# CW6680E_LQFP48_BT_Boombox_S10_V1_0.net
KiCad netlist of a schematic drawn in Altium Designer
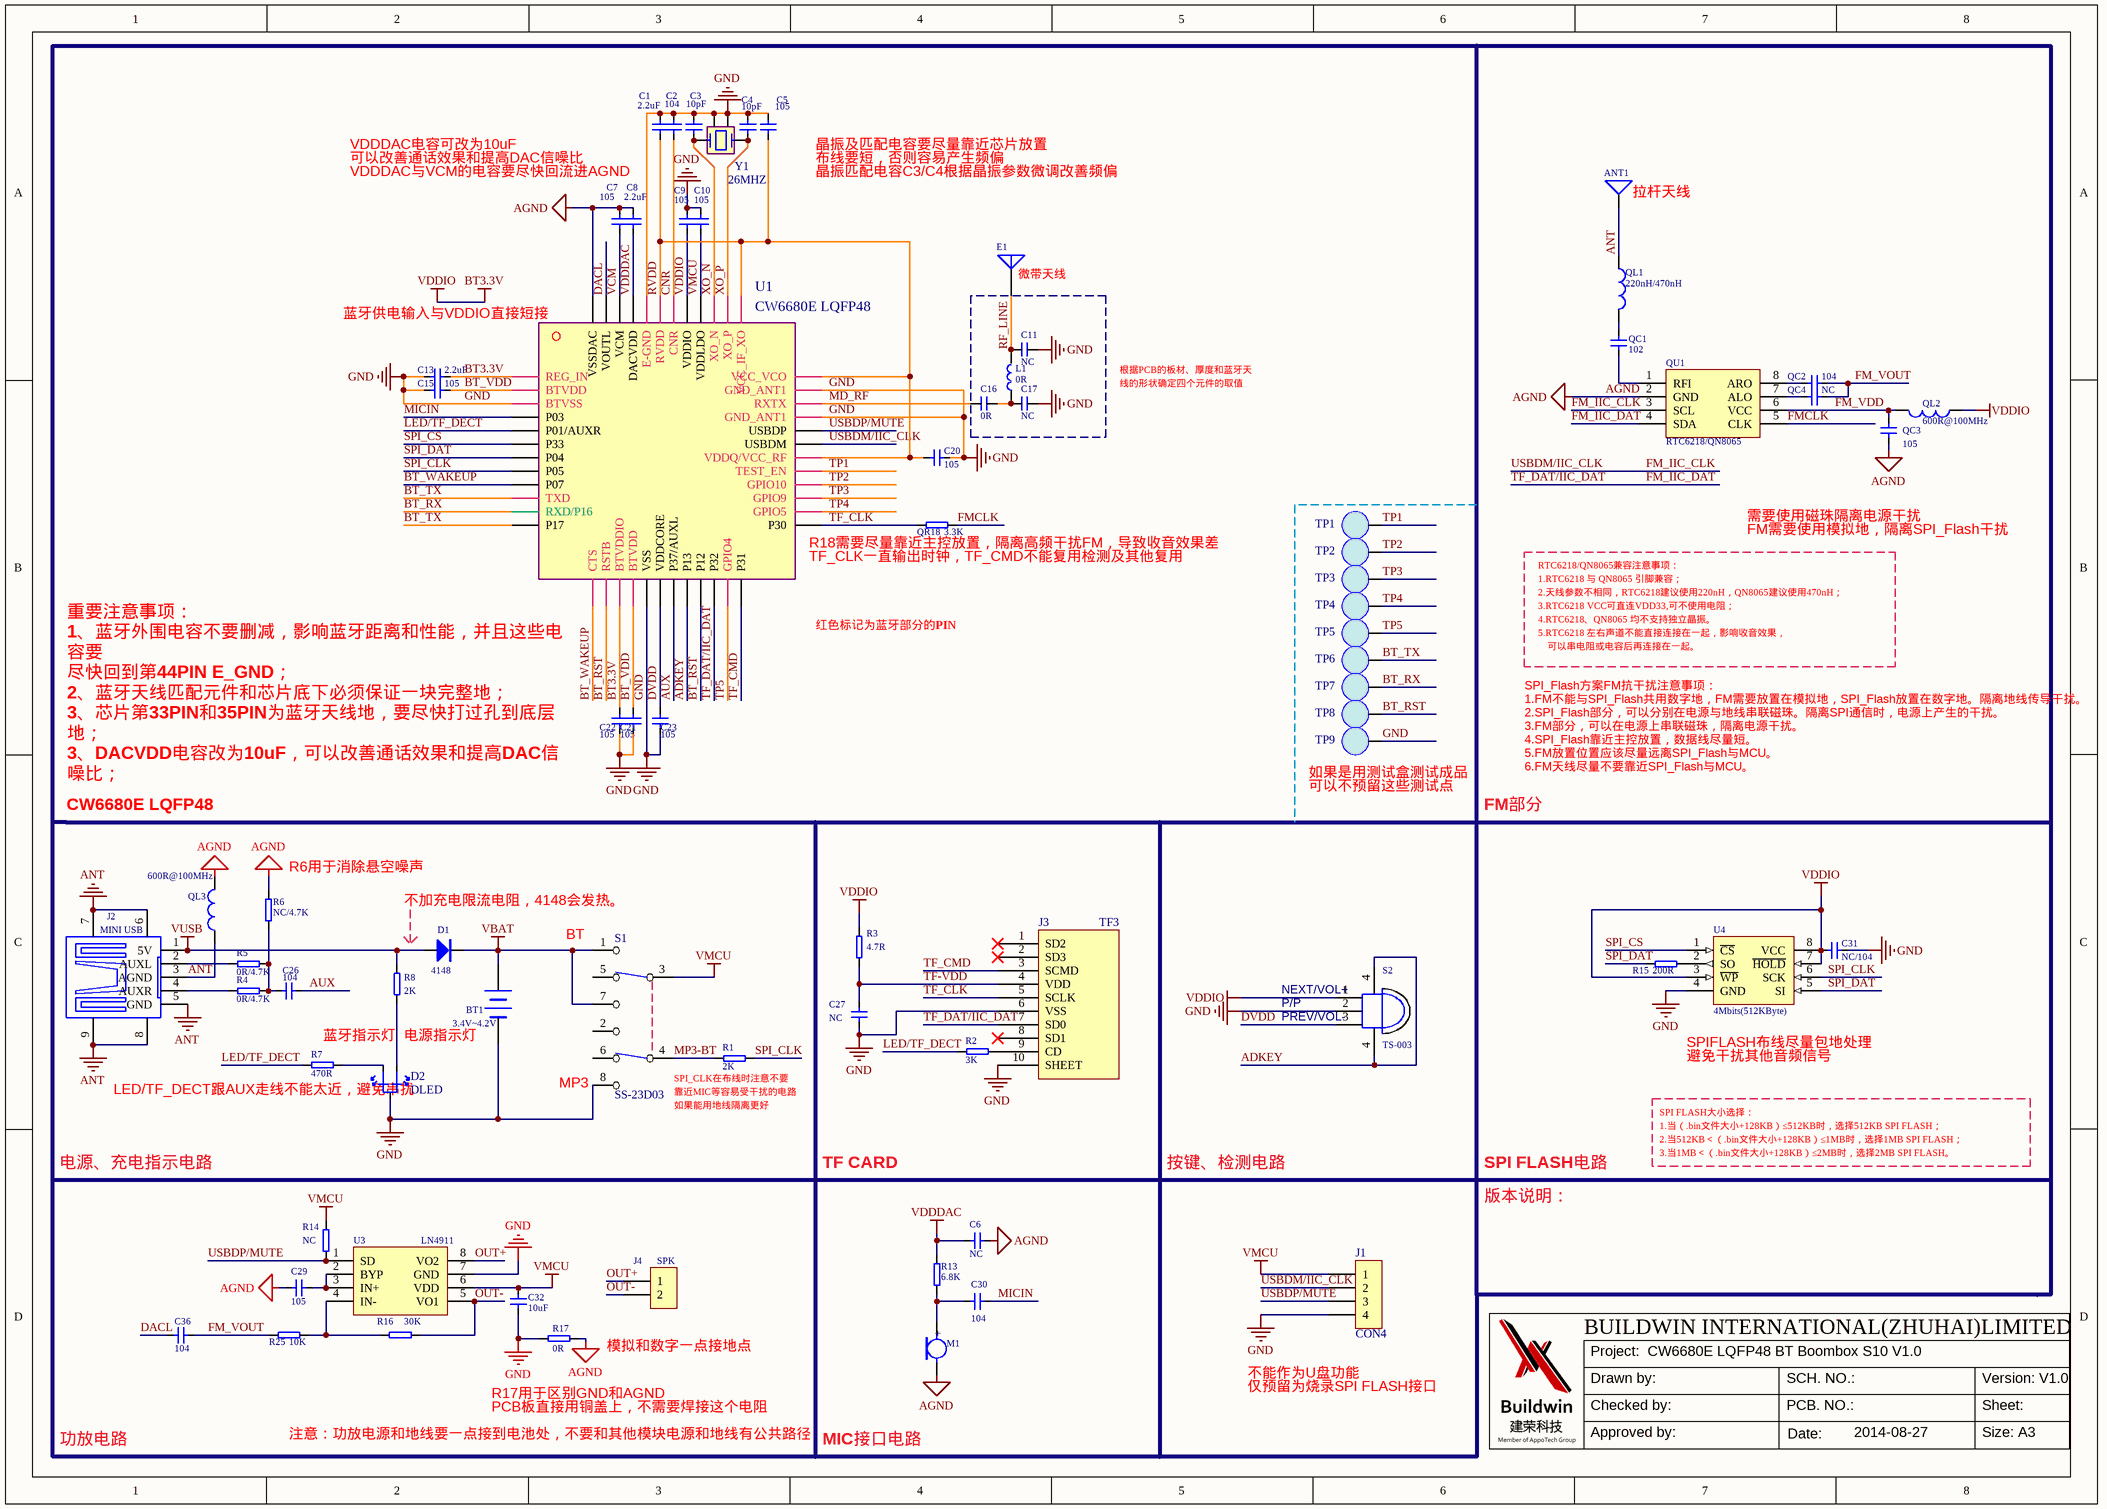
[diagram p0: CW6680E LQFP48 BT Boombox S10 V1.0.SchDoc]

(export (version "E")
  (design (tool "Eeschema 10.0.6"))
  (components
    (comp (ref "ANT1") (value "~") (footprint "ANT") (libsource (lib "*") (part "ANT")))
    (comp (ref "BT1")
      (value "3.4V~4.2V")
      (footprint "SIP2")
      (description "Battery")
      (libsource (lib "*") (part "BATTERY"))
    )
    (comp (ref "C1")
      (value "2.2uF")
      (footprint "C0603")
      (description "Capacitor")
      (libsource (lib "Common SCH") (part "CAP"))
    )
    (comp (ref "C2")
      (value "104")
      (footprint "C0603")
      (description "Capacitor")
      (libsource (lib "Common SCH") (part "CAP"))
    )
    (comp (ref "C3")
      (value "10pF")
      (footprint "C0603")
      (description "Capacitor")
      (libsource (lib "Common SCH") (part "CAP"))
    )
    (comp (ref "C4")
      (value "10pF")
      (footprint "C0603")
      (description "Capacitor")
      (libsource (lib "Common SCH") (part "CAP"))
    )
    (comp (ref "C5")
      (value "105")
      (footprint "C0603")
      (description "Capacitor")
      (libsource (lib "Common SCH") (part "CAP"))
    )
    (comp (ref "C6")
      (value "NC")
      (footprint "C0603")
      (description "Capacitor")
      (libsource (lib "*") (part "CAP"))
    )
    (comp (ref "C7")
      (value "105")
      (footprint "C0603")
      (description "Capacitor")
      (libsource (lib "Common SCH") (part "CAP"))
    )
    (comp (ref "C8")
      (value "2.2uF")
      (footprint "C0603")
      (description "Capacitor")
      (libsource (lib "Common SCH") (part "CAP"))
    )
    (comp (ref "C9")
      (value "105")
      (footprint "C0603")
      (description "Capacitor")
      (libsource (lib "Common SCH") (part "CAP"))
    )
    (comp (ref "C10")
      (value "105")
      (footprint "C0603")
      (description "Capacitor")
      (libsource (lib "Common SCH") (part "CAP"))
    )
    (comp (ref "C11")
      (value "NC")
      (footprint "C0603")
      (description "0402 CER CAP NCpF 50V +/-10%")
      (libsource (lib "*") (part "CAP_C"))
    )
    (comp (ref "C13")
      (value "2.2uF")
      (footprint "C0603")
      (description "Capacitor")
      (libsource (lib "Common SCH") (part "CAP"))
    )
    (comp (ref "C15")
      (value "105")
      (footprint "C0603")
      (description "Capacitor")
      (libsource (lib "Common SCH") (part "CAP"))
    )
    (comp (ref "C16")
      (value "0R")
      (footprint "C0603")
      (description "0402 CER CAP ?pF 50V +/-10%")
      (libsource (lib "*") (part "CAP_C"))
    )
    (comp (ref "C17")
      (value "NC")
      (footprint "C0603")
      (description "0402 CER CAP NCpF 50V +/-10%")
      (libsource (lib "*") (part "CAP_C"))
    )
    (comp (ref "C20")
      (value "105")
      (footprint "C0603")
      (description "Capacitor")
      (libsource (lib "Common SCH") (part "CAP"))
    )
    (comp (ref "C21")
      (value "105")
      (footprint "C0603")
      (description "Capacitor")
      (libsource (lib "*") (part "CAP"))
    )
    (comp (ref "C22")
      (value "105")
      (footprint "C0603")
      (description "Capacitor")
      (libsource (lib "*") (part "CAP"))
    )
    (comp (ref "C23")
      (value "105")
      (footprint "C0603")
      (description "Capacitor")
      (libsource (lib "Common SCH") (part "CAP"))
    )
    (comp (ref "C26")
      (value "104")
      (footprint "C0603")
      (description "Capacitor")
      (libsource (lib "*") (part "CAP"))
    )
    (comp (ref "C27")
      (value "NC")
      (footprint "C0603")
      (description "Capacitor")
      (libsource (lib "*") (part "CAP"))
    )
    (comp (ref "C29")
      (value "105")
      (footprint "C0603")
      (description "Capacitor")
      (libsource (lib "*") (part "CAP"))
    )
    (comp (ref "C30")
      (value "104")
      (footprint "C0603")
      (description "Capacitor")
      (libsource (lib "*") (part "CAP"))
    )
    (comp (ref "C31")
      (value "NC/104")
      (footprint "C0603")
      (description "Capacitor")
      (libsource (lib "Common SCH") (part "CAP"))
    )
    (comp (ref "C32")
      (value "10uF")
      (footprint "C0805")
      (description "Capacitor")
      (libsource (lib "*") (part "CAP"))
    )
    (comp (ref "C36")
      (value "104")
      (footprint "C0603")
      (description "Capacitor")
      (libsource (lib "*") (part "CAP"))
    )
    (comp (ref "D1")
      (value "4148")
      (footprint "DO-214")
      (description "Diode")
      (libsource (lib "*") (part "DIODE"))
    )
    (comp (ref "D2")
      (value "DLED")
      (footprint "LED-R&B")
      (description "双色灯 插件 共阴")
      (libsource (lib "LHLC-BDG-8051-V1.0") (part "DLED"))
    )
    (comp (ref "E1")
      (value "~")
      (footprint "ant_pifa")
      (description "Generic Antenna")
      (fields (field (name "PUBLISHER") "Altium Limited"))
      (libsource (lib "*") (part "Antenna"))
    )
    (comp (ref "J1")
      (value "CON4")
      (footprint "SIP4")
      (description "Connector")
      (libsource (lib "BW CONNECTOR SCH") (part "CON4"))
    )
    (comp (ref "J2")
      (value "MINI USB")
      (footprint "MINI-USB-B")
      (libsource (lib "BW SCH") (part "Mini USB-F"))
    )
    (comp (ref "J3") (value "TF3") (footprint "TFCARD") (libsource (lib "*") (part "TF")))
    (comp (ref "J4")
      (value "SPK")
      (footprint "SIP2")
      (description "Connector")
      (libsource (lib "*") (part "CON2"))
    )
    (comp (ref "L1")
      (value "0R")
      (footprint "L0603")
      (description "0 OHM")
      (libsource (lib "*") (part "INDUCTOR"))
    )
    (comp (ref "M1")
      (value "MIC")
      (footprint "MIC-4022")
      (description "Microphone")
      (libsource (lib "*") (part "MICROPHONE2"))
    )
    (comp (ref "QC1")
      (value "102")
      (footprint "C0603")
      (description "Capacitor")
      (libsource (lib "") (part "CAP_1"))
    )
    (comp (ref "QC2")
      (value "104")
      (footprint "C0603")
      (description "Capacitor")
      (libsource (lib "") (part "CAP_2"))
    )
    (comp (ref "QC3")
      (value "105")
      (footprint "C0603")
      (description "Capacitor")
      (libsource (lib "") (part "CAP_2"))
    )
    (comp (ref "QC4")
      (value "NC")
      (footprint "C0603")
      (description "Capacitor")
      (libsource (lib "") (part "CAP_2"))
    )
    (comp (ref "QL1") (value "220nH/470nH") (footprint "L0603") (libsource (lib "") (part "INDUCTOR_1")))
    (comp (ref "QL2") (value "600R@100MHz") (footprint "L0603") (libsource (lib "") (part "INDUCTOR_3")))
    (comp (ref "QL3") (value "600R@100MHz") (footprint "L0603") (libsource (lib "") (part "INDUCTOR_2")))
    (comp (ref "QR18") (value "3.3K") (footprint "R0603") (libsource (lib "*") (part "RES2")))
    (comp (ref "QU1")
      (value "RTC6218/QN8065")
      (footprint "SO-8")
      (libsource (lib "AX2053B Cola Demo V1.2") (part "QN8075"))
    )
    (comp (ref "R1") (value "2K") (footprint "R0603") (libsource (lib "*") (part "RES2")))
    (comp (ref "R2") (value "3K") (footprint "R0603") (libsource (lib "*") (part "RES2")))
    (comp (ref "R3") (value "4.7R") (footprint "R0603") (libsource (lib "*") (part "RES2")))
    (comp (ref "R4") (value "0R/4.7K") (footprint "R0603") (libsource (lib "*") (part "RES2")))
    (comp (ref "R5") (value "0R/4.7K") (footprint "R0603") (libsource (lib "*") (part "RES2")))
    (comp (ref "R6") (value "NC/4.7K") (footprint "R0603") (libsource (lib "*") (part "RES2")))
    (comp (ref "R7") (value "470R") (footprint "R0603") (libsource (lib "*") (part "RES2")))
    (comp (ref "R8") (value "2K") (footprint "R0603") (libsource (lib "*") (part "RES2")))
    (comp (ref "R13") (value "6.8K") (footprint "R0603") (libsource (lib "*") (part "RES2")))
    (comp (ref "R14") (value "NC") (footprint "R0603") (libsource (lib "*") (part "RES2")))
    (comp (ref "R15") (value "200R") (footprint "R0603") (libsource (lib "Common SCH") (part "RES2")))
    (comp (ref "R16") (value "30K") (footprint "R0603") (libsource (lib "*") (part "RES2")))
    (comp (ref "R17") (value "0R") (footprint "R0603") (libsource (lib "") (part "RES2_1")))
    (comp (ref "R25") (value "10K") (footprint "R0603") (libsource (lib "*") (part "RES2")))
    (comp (ref "S1")
      (value "SS-23D03")
      (footprint "3ND")
      (libsource (lib "S10-（AX2227+CW6639）V1.0") (part "SW-DPST"))
    )
    (comp (ref "S2") (value "TS-003") (footprint "KEY_BL") (libsource (lib "Schlib1") (part "TS-003")))
    (comp (ref "TP1")
      (value "TestPoint")
      (footprint "TP01")
      (libsource (lib "buildwin_BT") (part "TestPoint"))
    )
    (comp (ref "TP2")
      (value "TestPoint")
      (footprint "TP01")
      (libsource (lib "buildwin_BT") (part "TestPoint"))
    )
    (comp (ref "TP3")
      (value "TestPoint")
      (footprint "TP01")
      (libsource (lib "buildwin_BT") (part "TestPoint"))
    )
    (comp (ref "TP4")
      (value "TestPoint")
      (footprint "TP01")
      (libsource (lib "buildwin_BT") (part "TestPoint"))
    )
    (comp (ref "TP5")
      (value "TestPoint")
      (footprint "TP01")
      (libsource (lib "buildwin_BT") (part "TestPoint"))
    )
    (comp (ref "TP6")
      (value "TestPoint")
      (footprint "TP01")
      (libsource (lib "buildwin_BT") (part "TestPoint"))
    )
    (comp (ref "TP7")
      (value "TestPoint")
      (footprint "TP01")
      (libsource (lib "buildwin_BT") (part "TestPoint"))
    )
    (comp (ref "TP8")
      (value "TestPoint")
      (footprint "TP01")
      (libsource (lib "buildwin_BT") (part "TestPoint"))
    )
    (comp (ref "TP9")
      (value "TestPoint")
      (footprint "TP01")
      (libsource (lib "buildwin_BT") (part "TestPoint"))
    )
    (comp (ref "U1") (value "CW6680E LQFP48") (footprint "LQFP48-7*7") (libsource (lib "*") (part "BT8202")))
    (comp (ref "U3") (value "LN4911") (footprint "SO-8") (libsource (lib "*") (part "4871")))
    (comp (ref "U4")
      (value "4Mbits(512KByte)")
      (footprint "SO-8/8W")
      (libsource (lib "*") (part "SPI FLASH"))
    )
    (comp (ref "Y1") (value "26MHZ") (footprint "26m") (libsource (lib "*") (part "26MHZ")))
  )
  (nets
    (net (code "2") (name "/ADKEY") (class "Default")
      (node (ref "S2") (pin "4") (pinfunction "4_4") (pintype "passive"))
      (node (ref "U1") (pin "20") (pinfunction "P13_20") (pintype "passive"))
    )
    (net (code "3") (name "/AUX") (class "Default")
      (node (ref "C26") (pin "1") (pinfunction "1_1") (pintype "passive"))
      (node (ref "U1") (pin "19") (pinfunction "P37/AUXL_19") (pintype "passive"))
    )
    (net (code "4") (name "/BT_RST") (class "Default")
      (node (ref "TP8") (pin "1") (pinfunction "1_1") (pintype "power_in"))
      (node (ref "U1") (pin "14") (pinfunction "RSTB_14") (pintype "passive"))
      (node (ref "U1") (pin "21") (pinfunction "P12_21") (pintype "passive"))
    )
    (net (code "5") (name "/BT_RX") (class "Default")
      (node (ref "TP7") (pin "1") (pinfunction "1_1") (pintype "power_in"))
      (node (ref "U1") (pin "11") (pinfunction "RXD/P16_11") (pintype "passive"))
    )
    (net (code "6") (name "/BT_TX") (class "Default")
      (node (ref "TP6") (pin "1") (pinfunction "1_1") (pintype "power_in"))
      (node (ref "U1") (pin "10") (pinfunction "TXD_10") (pintype "passive"))
      (node (ref "U1") (pin "12") (pinfunction "P17_12") (pintype "passive"))
    )
    (net (code "7") (name "/BT_VDD") (class "Default")
      (node (ref "C15") (pin "2") (pinfunction "2_2") (pintype "passive"))
      (node (ref "C21") (pin "1") (pinfunction "1_1") (pintype "passive"))
      (node (ref "U1") (pin "16") (pinfunction "BTVDD_16") (pintype "passive"))
      (node (ref "U1") (pin "2") (pinfunction "BTVDD_2") (pintype "passive"))
    )
    (net (code "8") (name "/BT_WAKEUP") (class "Default")
      (node (ref "U1") (pin "13") (pinfunction "CTS_13") (pintype "passive"))
      (node (ref "U1") (pin "9") (pinfunction "P07_9") (pintype "passive"))
    )
    (net (code "9") (name "/CNR") (class "Default")
      (node (ref "C2") (pin "1") (pinfunction "1_1") (pintype "passive"))
      (node (ref "U1") (pin "42") (pinfunction "CNR_42") (pintype "passive"))
    )
    (net (code "10") (name "/DACL") (class "Default")
      (node (ref "C36") (pin "1") (pinfunction "1_1") (pintype "passive"))
      (node (ref "U1") (pin "47") (pinfunction "VOUTL_47") (pintype "passive"))
    )
    (net (code "11") (name "/DVDD") (class "Default")
      (node (ref "C23") (pin "1") (pinfunction "1_1") (pintype "passive"))
      (node (ref "S2") (pin "3") (pinfunction "3_3") (pintype "passive"))
      (node (ref "U1") (pin "18") (pinfunction "VDDCORE_18") (pintype "passive"))
    )
    (net (code "12") (name "/FMCLK") (class "Default")
      (node (ref "QR18") (pin "1") (pinfunction "1_1") (pintype "passive"))
      (node (ref "QU1") (pin "5") (pinfunction "CLK_5") (pintype "passive"))
    )
    (net (code "13") (name "/FM_IIC_CLK") (class "Default")
      (node (ref "J1") (pin "2") (pinfunction "2_2") (pintype "passive"))
      (node (ref "QU1") (pin "3") (pinfunction "SCL_3") (pintype "passive"))
      (node (ref "U1") (pin "31") (pinfunction "USBDM_31") (pintype "passive"))
    )
    (net (code "14") (name "/FM_IIC_DAT") (class "Default")
      (node (ref "J3") (pin "7") (pinfunction "SD0_7") (pintype "passive"))
      (node (ref "QU1") (pin "4") (pinfunction "SDA_4") (pintype "passive"))
      (node (ref "U1") (pin "22") (pinfunction "P32_22") (pintype "passive"))
    )
    (net (code "15") (name "/FM_VDD") (class "Default")
      (node (ref "QC3") (pin "1") (pinfunction "1_1") (pintype "passive"))
      (node (ref "QL2") (pin "1") (pinfunction "1_1") (pintype "passive"))
      (node (ref "QU1") (pin "6") (pinfunction "VCC_6") (pintype "passive"))
    )
    (net (code "16") (name "/FM_VOUT") (class "Default")
      (node (ref "C36") (pin "2") (pinfunction "2_2") (pintype "passive"))
      (node (ref "QC2") (pin "1") (pinfunction "1_1") (pintype "passive"))
      (node (ref "QC4") (pin "1") (pinfunction "1_1") (pintype "passive"))
      (node (ref "R25") (pin "2") (pinfunction "2_2") (pintype "passive"))
    )
    (net (code "17") (name "/LED{slash}TF_DECT") (class "Default")
      (node (ref "R2") (pin "1") (pinfunction "1_1") (pintype "passive"))
      (node (ref "R7") (pin "2") (pinfunction "2_2") (pintype "passive"))
      (node (ref "U1") (pin "5") (pinfunction "P01/AUXR_5") (pintype "passive"))
    )
    (net (code "18") (name "/MD_RF") (class "Default")
      (node (ref "C16") (pin "2") (pintype "passive"))
      (node (ref "U1") (pin "34") (pinfunction "RXTX_34") (pintype "passive"))
    )
    (net (code "19") (name "/MICIN") (class "Default")
      (node (ref "C30") (pin "1") (pinfunction "1_1") (pintype "passive"))
      (node (ref "U1") (pin "4") (pinfunction "P03_4") (pintype "passive"))
    )
    (net (code "20") (name "/MP3-BT") (class "Default")
      (node (ref "R1") (pin "2") (pinfunction "2_2") (pintype "passive"))
      (node (ref "S1") (pin "4") (pinfunction "4_4") (pintype "passive"))
    )
    (net (code "21") (name "/OUT+") (class "Default")
      (node (ref "J4") (pin "1") (pinfunction "1_1") (pintype "passive"))
      (node (ref "U3") (pin "8") (pinfunction "VO2_8") (pintype "passive"))
    )
    (net (code "22") (name "/OUT-") (class "Default")
      (node (ref "J4") (pin "2") (pinfunction "2_2") (pintype "passive"))
      (node (ref "R16") (pin "1") (pinfunction "1_1") (pintype "passive"))
      (node (ref "U3") (pin "5") (pinfunction "VO1_5") (pintype "passive"))
    )
    (net (code "23") (name "/RF_LINE") (class "Default")
      (node (ref "C11") (pin "1") (pintype "passive"))
      (node (ref "E1") (pin "1") (pinfunction "A_1") (pintype "passive"))
      (node (ref "L1") (pin "2") (pinfunction "2_2") (pintype "passive"))
    )
    (net (code "24") (name "/RVDD") (class "Default")
      (node (ref "C1") (pin "1") (pinfunction "1_1") (pintype "passive"))
      (node (ref "C20") (pin "1") (pinfunction "1_1") (pintype "passive"))
      (node (ref "C5") (pin "2") (pinfunction "2_2") (pintype "passive"))
      (node (ref "U1") (pin "30") (pinfunction "VDDQ/VCC_RF_30") (pintype "passive"))
      (node (ref "U1") (pin "36") (pinfunction "VCC_VCO_36") (pintype "passive"))
      (node (ref "U1") (pin "37") (pinfunction "VCC_IF_XO_37") (pintype "passive"))
      (node (ref "U1") (pin "43") (pinfunction "RVDD_43") (pintype "passive"))
    )
    (net (code "25") (name "/SPI_CLK") (class "Default")
      (node (ref "R1") (pin "1") (pinfunction "1_1") (pintype "passive"))
      (node (ref "U1") (pin "8") (pinfunction "P05_8") (pintype "passive"))
      (node (ref "U4") (pin "6") (pinfunction "SCK_6") (pintype "input"))
    )
    (net (code "26") (name "/SPI_CS") (class "Default")
      (node (ref "U1") (pin "6") (pinfunction "P33_6") (pintype "passive"))
      (node (ref "U4") (pin "1") (pinfunction "~{CS}_1") (pintype "input"))
    )
    (net (code "27") (name "/SPI_DAT") (class "Default")
      (node (ref "R15") (pin "2") (pinfunction "2_2") (pintype "passive"))
      (node (ref "U1") (pin "7") (pinfunction "P04_7") (pintype "passive"))
      (node (ref "U4") (pin "5") (pinfunction "SI_5") (pintype "input"))
    )
    (net (code "28") (name "/TF-VDD") (class "Default")
      (node (ref "C27") (pin "1") (pinfunction "1_1") (pintype "passive"))
      (node (ref "J3") (pin "4") (pinfunction "VDD_4") (pintype "passive"))
      (node (ref "R3") (pin "1") (pinfunction "1_1") (pintype "passive"))
    )
    (net (code "29") (name "/TF_CLK") (class "Default")
      (node (ref "J3") (pin "5") (pinfunction "SCLK_5") (pintype "passive"))
      (node (ref "QR18") (pin "2") (pinfunction "2_2") (pintype "passive"))
      (node (ref "U1") (pin "25") (pinfunction "P30_25") (pintype "passive"))
    )
    (net (code "30") (name "/TF_CMD") (class "Default")
      (node (ref "J3") (pin "3") (pinfunction "SCMD_3") (pintype "passive"))
      (node (ref "U1") (pin "24") (pinfunction "P31_24") (pintype "passive"))
    )
    (net (code "31") (name "/TP1") (class "Default")
      (node (ref "TP1") (pin "1") (pinfunction "1_1") (pintype "power_in"))
      (node (ref "U1") (pin "29") (pinfunction "TEST_EN_29") (pintype "passive"))
    )
    (net (code "32") (name "/TP2") (class "Default")
      (node (ref "TP2") (pin "1") (pinfunction "1_1") (pintype "power_in"))
      (node (ref "U1") (pin "28") (pinfunction "GPIO10_28") (pintype "passive"))
    )
    (net (code "33") (name "/TP3") (class "Default")
      (node (ref "TP3") (pin "1") (pinfunction "1_1") (pintype "power_in"))
      (node (ref "U1") (pin "27") (pinfunction "GPIO9_27") (pintype "passive"))
    )
    (net (code "34") (name "/TP4") (class "Default")
      (node (ref "TP4") (pin "1") (pinfunction "1_1") (pintype "power_in"))
      (node (ref "U1") (pin "26") (pinfunction "GPIO5_26") (pintype "passive"))
    )
    (net (code "35") (name "/TP5") (class "Default")
      (node (ref "TP5") (pin "1") (pinfunction "1_1") (pintype "power_in"))
      (node (ref "U1") (pin "23") (pinfunction "GPIO4_23") (pintype "passive"))
    )
    (net (code "36") (name "/USBDP{slash}MUTE") (class "Default")
      (node (ref "J1") (pin "3") (pinfunction "3_3") (pintype "passive"))
      (node (ref "R14") (pin "1") (pinfunction "1_1") (pintype "passive"))
      (node (ref "U1") (pin "32") (pinfunction "USBDP_32") (pintype "passive"))
      (node (ref "U3") (pin "1") (pinfunction "SD_1") (pintype "passive"))
    )
    (net (code "37") (name "/VCM") (class "Default")
      (node (ref "C7") (pin "2") (pinfunction "2_2") (pintype "passive"))
      (node (ref "U1") (pin "46") (pinfunction "VCM_46") (pintype "passive"))
    )
    (net (code "38") (name "/XO_N") (class "Default")
      (node (ref "C3") (pin "2") (pinfunction "2_2") (pintype "passive"))
      (node (ref "U1") (pin "39") (pinfunction "XO_N_39") (pintype "passive"))
      (node (ref "Y1") (pin "1") (pinfunction "1_1") (pintype "passive"))
    )
    (net (code "39") (name "/XO_P") (class "Default")
      (node (ref "C4") (pin "2") (pinfunction "2_2") (pintype "passive"))
      (node (ref "U1") (pin "38") (pinfunction "XO_P_38") (pintype "passive"))
      (node (ref "Y1") (pin "3") (pinfunction "3_3") (pintype "passive"))
    )
    (net (code "40") (name "AGND") (class "Default")
      (node (ref "C29") (pin "2") (pinfunction "2_2") (pintype "passive"))
      (node (ref "C6") (pin "2") (pinfunction "2_2") (pintype "passive"))
      (node (ref "C7") (pin "1") (pinfunction "1_1") (pintype "passive"))
      (node (ref "C8") (pin "1") (pinfunction "1_1") (pintype "passive"))
      (node (ref "M1") (pin "2") (pinfunction "2_2") (pintype "passive"))
      (node (ref "QC3") (pin "2") (pinfunction "2_2") (pintype "passive"))
      (node (ref "QL3") (pin "1") (pinfunction "1_1") (pintype "passive"))
      (node (ref "QU1") (pin "2") (pinfunction "GND_2") (pintype "passive"))
      (node (ref "R17") (pin "2") (pinfunction "2_2") (pintype "passive"))
      (node (ref "R6") (pin "2") (pinfunction "2_2") (pintype "passive"))
      (node (ref "U1") (pin "48") (pinfunction "VSSDAC_48") (pintype "passive"))
    )
    (net (code "41") (name "ANT") (class "Default")
      (node (ref "ANT1") (pin "1") (pintype "passive"))
      (node (ref "J2") (pin "3") (pinfunction "AGND_3") (pintype "passive"))
      (node (ref "J2") (pin "5") (pinfunction "GND_5") (pintype "passive"))
      (node (ref "J2") (pin "6") (pintype "passive"))
      (node (ref "J2") (pin "7") (pintype "passive"))
      (node (ref "J2") (pin "8") (pintype "passive"))
      (node (ref "J2") (pin "9") (pintype "passive"))
      (node (ref "QL1") (pin "1") (pinfunction "1_1") (pintype "passive"))
      (node (ref "QL3") (pin "2") (pinfunction "2_2") (pintype "passive"))
    )
    (net (code "42") (name "BT3.3V") (class "Default")
      (node (ref "C13") (pin "2") (pinfunction "2_2") (pintype "passive"))
      (node (ref "C22") (pin "1") (pinfunction "1_1") (pintype "passive"))
      (node (ref "C31") (pin "2") (pinfunction "2_2") (pintype "passive"))
      (node (ref "C9") (pin "2") (pinfunction "2_2") (pintype "passive"))
      (node (ref "QL2") (pin "2") (pinfunction "2_2") (pintype "passive"))
      (node (ref "R3") (pin "2") (pinfunction "2_2") (pintype "passive"))
      (node (ref "S2") (pin "1") (pinfunction "1_1") (pintype "passive"))
      (node (ref "U1") (pin "1") (pinfunction "REG_IN_1") (pintype "passive"))
      (node (ref "U1") (pin "15") (pinfunction "BTVDDIO_15") (pintype "passive"))
      (node (ref "U1") (pin "41") (pinfunction "VDDIO_41") (pintype "passive"))
      (node (ref "U4") (pin "3") (pinfunction "~{WP}_3") (pintype "input"))
      (node (ref "U4") (pin "7") (pinfunction "~{HOLD}_7") (pintype "input"))
      (node (ref "U4") (pin "8") (pinfunction "VCC_8") (pintype "power_in"))
    )
    (net (code "43") (name "GND") (class "Default")
      (node (ref "BT1") (pin "2") (pinfunction "-_2") (pintype "passive"))
      (node (ref "C1") (pin "2") (pinfunction "2_2") (pintype "passive"))
      (node (ref "C10") (pin "1") (pinfunction "1_1") (pintype "passive"))
      (node (ref "C11") (pin "2") (pintype "passive"))
      (node (ref "C13") (pin "1") (pinfunction "1_1") (pintype "passive"))
      (node (ref "C15") (pin "1") (pinfunction "1_1") (pintype "passive"))
      (node (ref "C17") (pin "2") (pintype "passive"))
      (node (ref "C2") (pin "2") (pinfunction "2_2") (pintype "passive"))
      (node (ref "C20") (pin "2") (pinfunction "2_2") (pintype "passive"))
      (node (ref "C21") (pin "2") (pinfunction "2_2") (pintype "passive"))
      (node (ref "C22") (pin "2") (pinfunction "2_2") (pintype "passive"))
      (node (ref "C23") (pin "2") (pinfunction "2_2") (pintype "passive"))
      (node (ref "C27") (pin "2") (pinfunction "2_2") (pintype "passive"))
      (node (ref "C3") (pin "1") (pinfunction "1_1") (pintype "passive"))
      (node (ref "C31") (pin "1") (pinfunction "1_1") (pintype "passive"))
      (node (ref "C32") (pin "1") (pinfunction "1_1") (pintype "passive"))
      (node (ref "C4") (pin "1") (pinfunction "1_1") (pintype "passive"))
      (node (ref "C5") (pin "1") (pinfunction "1_1") (pintype "passive"))
      (node (ref "C9") (pin "1") (pinfunction "1_1") (pintype "passive"))
      (node (ref "D2") (pin "2") (pinfunction "2_2") (pintype "passive"))
      (node (ref "J1") (pin "4") (pinfunction "4_4") (pintype "passive"))
      (node (ref "J3") (pin "10") (pinfunction "SHEET_10") (pintype "passive"))
      (node (ref "J3") (pin "6") (pinfunction "VSS_6") (pintype "passive"))
      (node (ref "R17") (pin "1") (pinfunction "1_1") (pintype "passive"))
      (node (ref "S1") (pin "8") (pinfunction "8_8") (pintype "passive"))
      (node (ref "S2") (pin "2") (pinfunction "2_2") (pintype "passive"))
      (node (ref "TP9") (pin "1") (pinfunction "1_1") (pintype "power_in"))
      (node (ref "U1") (pin "17") (pinfunction "VSS_17") (pintype "passive"))
      (node (ref "U1") (pin "3") (pinfunction "BTVSS_3") (pintype "passive"))
      (node (ref "U1") (pin "33") (pinfunction "GND_ANT1_33") (pintype "passive"))
      (node (ref "U1") (pin "35") (pinfunction "GND_ANT1_35") (pintype "passive"))
      (node (ref "U1") (pin "44") (pinfunction "E-GND_44") (pintype "passive"))
      (node (ref "U3") (pin "7") (pinfunction "GND_7") (pintype "passive"))
      (node (ref "U4") (pin "4") (pinfunction "GND_4") (pintype "power_in"))
      (node (ref "Y1") (pin "2") (pintype "passive"))
      (node (ref "Y1") (pin "4") (pintype "passive"))
    )
    (net (code "44") (name "Net-(C16-Pad1)") (class "Default")
      (node (ref "C16") (pin "1") (pintype "passive"))
      (node (ref "C17") (pin "1") (pintype "passive"))
      (node (ref "L1") (pin "1") (pinfunction "1_1") (pintype "passive"))
    )
    (net (code "45") (name "Net-(C26-Pad2)") (class "Default")
      (node (ref "C26") (pin "2") (pinfunction "2_2") (pintype "passive"))
      (node (ref "R4") (pin "1") (pinfunction "1_1") (pintype "passive"))
      (node (ref "R5") (pin "1") (pinfunction "1_1") (pintype "passive"))
      (node (ref "R6") (pin "1") (pinfunction "1_1") (pintype "passive"))
    )
    (net (code "46") (name "Net-(C30-Pad2)") (class "Default")
      (node (ref "C30") (pin "2") (pinfunction "2_2") (pintype "passive"))
      (node (ref "M1") (pin "1") (pinfunction "1_1") (pintype "passive"))
      (node (ref "R13") (pin "2") (pinfunction "2_2") (pintype "passive"))
    )
    (net (code "47") (name "Net-(D2-Pad1)") (class "Default")
      (node (ref "D2") (pin "1") (pinfunction "1_1") (pintype "passive"))
      (node (ref "R7") (pin "1") (pinfunction "1_1") (pintype "passive"))
    )
    (net (code "48") (name "Net-(D2-Pad3)") (class "Default")
      (node (ref "D2") (pin "3") (pinfunction "3_3") (pintype "passive"))
      (node (ref "R8") (pin "1") (pinfunction "1_1") (pintype "passive"))
    )
    (net (code "49") (name "Net-(J2-AUXL)") (class "Default")
      (node (ref "J2") (pin "2") (pinfunction "AUXL_2") (pintype "passive"))
      (node (ref "R5") (pin "2") (pinfunction "2_2") (pintype "passive"))
    )
    (net (code "50") (name "Net-(J2-AUXR)") (class "Default")
      (node (ref "J2") (pin "4") (pinfunction "AUXR_4") (pintype "passive"))
      (node (ref "R4") (pin "2") (pinfunction "2_2") (pintype "passive"))
    )
    (net (code "51") (name "Net-(J3-CD)") (class "Default")
      (node (ref "J3") (pin "9") (pinfunction "CD_9") (pintype "passive"))
      (node (ref "R2") (pin "2") (pinfunction "2_2") (pintype "passive"))
    )
    (net (code "52") (name "Net-(QC1-Pad2)") (class "Default")
      (node (ref "QC1") (pin "2") (pinfunction "2_2") (pintype "passive"))
      (node (ref "QL1") (pin "2") (pinfunction "2_2") (pintype "passive"))
    )
    (net (code "53") (name "Net-(QU1-ALO)") (class "Default")
      (node (ref "QC4") (pin "2") (pinfunction "2_2") (pintype "passive"))
      (node (ref "QU1") (pin "7") (pinfunction "ALO_7") (pintype "passive"))
    )
    (net (code "54") (name "Net-(QU1-ARO)") (class "Default")
      (node (ref "QC2") (pin "2") (pinfunction "2_2") (pintype "passive"))
      (node (ref "QU1") (pin "8") (pinfunction "ARO_8") (pintype "passive"))
    )
    (net (code "55") (name "Net-(QU1-RFI)") (class "Default")
      (node (ref "QC1") (pin "1") (pinfunction "1_1") (pintype "passive"))
      (node (ref "QU1") (pin "1") (pinfunction "RFI_1") (pintype "passive"))
    )
    (net (code "56") (name "Net-(U3-BYP)") (class "Default")
      (node (ref "C29") (pin "1") (pinfunction "1_1") (pintype "passive"))
      (node (ref "U3") (pin "2") (pinfunction "BYP_2") (pintype "passive"))
      (node (ref "U3") (pin "3") (pinfunction "IN+_3") (pintype "passive"))
    )
    (net (code "57") (name "Net-(U3-IN-)") (class "Default")
      (node (ref "R16") (pin "2") (pinfunction "2_2") (pintype "passive"))
      (node (ref "R25") (pin "1") (pinfunction "1_1") (pintype "passive"))
      (node (ref "U3") (pin "4") (pinfunction "IN-_4") (pintype "passive"))
    )
    (net (code "58") (name "Net-(U4-SO)") (class "Default")
      (node (ref "R15") (pin "1") (pinfunction "1_1") (pintype "passive"))
      (node (ref "U4") (pin "2") (pinfunction "SO_2") (pintype "output"))
    )
    (net (code "59") (name "VBAT") (class "Default")
      (node (ref "BT1") (pin "1") (pinfunction "+_1") (pintype "passive"))
      (node (ref "D1") (pin "2") (pinfunction "K_2") (pintype "passive"))
      (node (ref "S1") (pin "1") (pinfunction "1_1") (pintype "passive"))
      (node (ref "S1") (pin "7") (pinfunction "7_7") (pintype "passive"))
    )
    (net (code "60") (name "VDDDAC") (class "Default")
      (node (ref "C6") (pin "1") (pinfunction "1_1") (pintype "passive"))
      (node (ref "C8") (pin "2") (pinfunction "2_2") (pintype "passive"))
      (node (ref "R13") (pin "1") (pinfunction "1_1") (pintype "passive"))
      (node (ref "U1") (pin "45") (pinfunction "DACVDD_45") (pintype "passive"))
    )
    (net (code "61") (name "VMCU") (class "Default")
      (node (ref "C10") (pin "2") (pinfunction "2_2") (pintype "passive"))
      (node (ref "C32") (pin "2") (pinfunction "2_2") (pintype "passive"))
      (node (ref "J1") (pin "1") (pinfunction "1_1") (pintype "passive"))
      (node (ref "R14") (pin "2") (pinfunction "2_2") (pintype "passive"))
      (node (ref "S1") (pin "3") (pinfunction "3_3") (pintype "passive"))
      (node (ref "U1") (pin "40") (pinfunction "VDDLDO_40") (pintype "passive"))
      (node (ref "U3") (pin "6") (pinfunction "VDD_6") (pintype "passive"))
    )
    (net (code "62") (name "VUSB") (class "Default")
      (node (ref "D1") (pin "1") (pinfunction "A_1") (pintype "passive"))
      (node (ref "J2") (pin "1") (pinfunction "5V_1") (pintype "passive"))
      (node (ref "R8") (pin "2") (pinfunction "2_2") (pintype "passive"))
    )
    (net (code "63") (name "unconnected-(J3-SD1-Pad8)") (class "Default")
      (node (ref "J3") (pin "8") (pinfunction "SD1_8") (pintype "passive+no_connect"))
    )
    (net (code "64") (name "unconnected-(J3-SD2-Pad1)") (class "Default")
      (node (ref "J3") (pin "1") (pinfunction "SD2_1") (pintype "passive+no_connect"))
    )
    (net (code "65") (name "unconnected-(J3-SD3-Pad2)") (class "Default")
      (node (ref "J3") (pin "2") (pinfunction "SD3_2") (pintype "passive+no_connect"))
    )
    (net (code "66") (name "unconnected-(S1-Pad2)") (class "Default")
      (node (ref "S1") (pin "2") (pinfunction "2_2") (pintype "passive"))
    )
    (net (code "67") (name "unconnected-(S1-Pad5)") (class "Default")
      (node (ref "S1") (pin "5") (pinfunction "5_5") (pintype "passive"))
    )
    (net (code "68") (name "unconnected-(S1-Pad6)") (class "Default")
      (node (ref "S1") (pin "6") (pinfunction "6_6") (pintype "passive"))
    )
  )
)
